# SCH_Font_conexion_LCD_display.net
KiCad netlist of a schematic drawn in Altium Designer
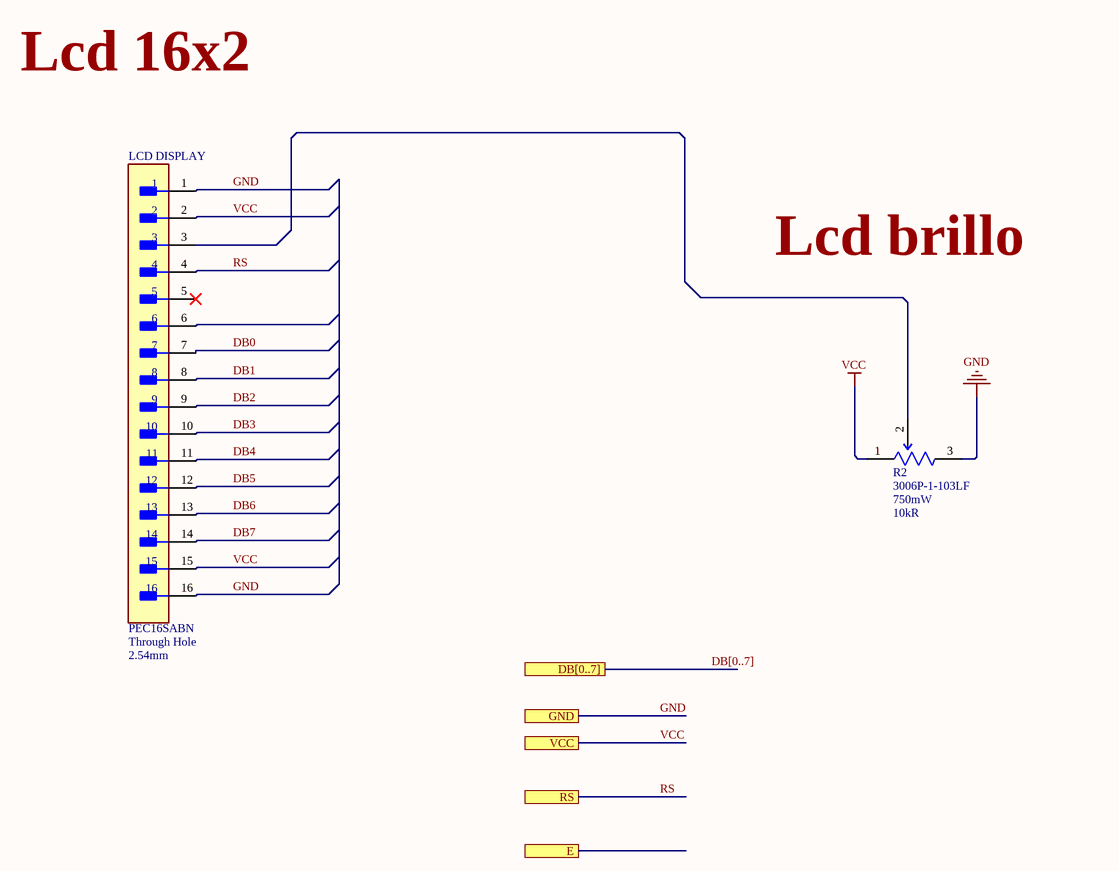
[diagram p0: SCH Font conexion LCD display.SchDoc]

(export (version "E")
  (design (tool "Eeschema 10.0.6"))
  (components
    (comp (ref "LCD DISPLAY")
      (value "PEC16SABN")
      (footprint "FP-PEC16SABN-MFG")
      (description "CONN HEADER VERT 16POS 2.54MM")
      (fields (field (name "MOUNT") "Through Hole") (field (name "HEIGHT") "2.54mm"))
      (libsource (lib "Altium Content Vault") (part "e5c9d856941f54a8fdb498ab6b27a18"))
    )
    (comp (ref "R2")
      (value "3006P-1-103LF")
      (footprint "FP-3006P-MFG")
      (description "TRIMMER 10KOHM 0.75W PC PIN SIDE")
      (fields
        (field (name "POWER RATING") "750mW")
        (field (name "TOLERANCE") "10%")
        (field (name "RESISTANCE") "10kR")
      )
      (libsource (lib "Altium Content Vault") (part "ad0de4570dda44d2fdef8f57041519a"))
    )
  )
  (nets
    (net (code "1") (name "/DB0") (class "Default")
      (node (ref "LCD DISPLAY") (pin "7") (pinfunction "7_7") (pintype "passive"))
    )
    (net (code "2") (name "/DB1") (class "Default")
      (node (ref "LCD DISPLAY") (pin "8") (pinfunction "8_8") (pintype "passive"))
    )
    (net (code "3") (name "/DB2") (class "Default")
      (node (ref "LCD DISPLAY") (pin "9") (pinfunction "9_9") (pintype "passive"))
    )
    (net (code "4") (name "/DB3") (class "Default")
      (node (ref "LCD DISPLAY") (pin "10") (pinfunction "10_10") (pintype "passive"))
    )
    (net (code "5") (name "/DB4") (class "Default")
      (node (ref "LCD DISPLAY") (pin "11") (pinfunction "11_11") (pintype "passive"))
    )
    (net (code "6") (name "/DB5") (class "Default")
      (node (ref "LCD DISPLAY") (pin "12") (pinfunction "12_12") (pintype "passive"))
    )
    (net (code "7") (name "/DB6") (class "Default")
      (node (ref "LCD DISPLAY") (pin "13") (pinfunction "13_13") (pintype "passive"))
    )
    (net (code "8") (name "/DB7") (class "Default")
      (node (ref "LCD DISPLAY") (pin "14") (pinfunction "14_14") (pintype "passive"))
    )
    (net (code "11") (name "/RS") (class "Default")
      (node (ref "LCD DISPLAY") (pin "4") (pinfunction "4_4") (pintype "passive"))
    )
    (net (code "12") (name "GND") (class "Default")
      (node (ref "LCD DISPLAY") (pin "1") (pinfunction "1_1") (pintype "passive"))
      (node (ref "LCD DISPLAY") (pin "16") (pinfunction "16_16") (pintype "passive"))
      (node (ref "R2") (pin "3") (pinfunction "CW_3") (pintype "passive"))
    )
    (net (code "13") (name "Net-(R2-WIPER)") (class "Default")
      (node (ref "LCD DISPLAY") (pin "3") (pinfunction "3_3") (pintype "passive"))
      (node (ref "R2") (pin "2") (pinfunction "WIPER_2") (pintype "passive"))
    )
    (net (code "14") (name "VCC") (class "Default")
      (node (ref "LCD DISPLAY") (pin "15") (pinfunction "15_15") (pintype "passive"))
      (node (ref "LCD DISPLAY") (pin "2") (pinfunction "2_2") (pintype "passive"))
      (node (ref "R2") (pin "1") (pinfunction "CCW_1") (pintype "passive"))
    )
    (net (code "15") (name "unconnected-(LCD DISPLAY-Pad5)") (class "Default")
      (node (ref "LCD DISPLAY") (pin "5") (pinfunction "5_5") (pintype "passive+no_connect"))
    )
    (net (code "16") (name "unconnected-(LCD DISPLAY-Pad6)") (class "Default")
      (node (ref "LCD DISPLAY") (pin "6") (pinfunction "6_6") (pintype "passive"))
    )
  )
)
